# PROC099B_LP_Connector.net
KiCad netlist of a schematic drawn in Altium Designer
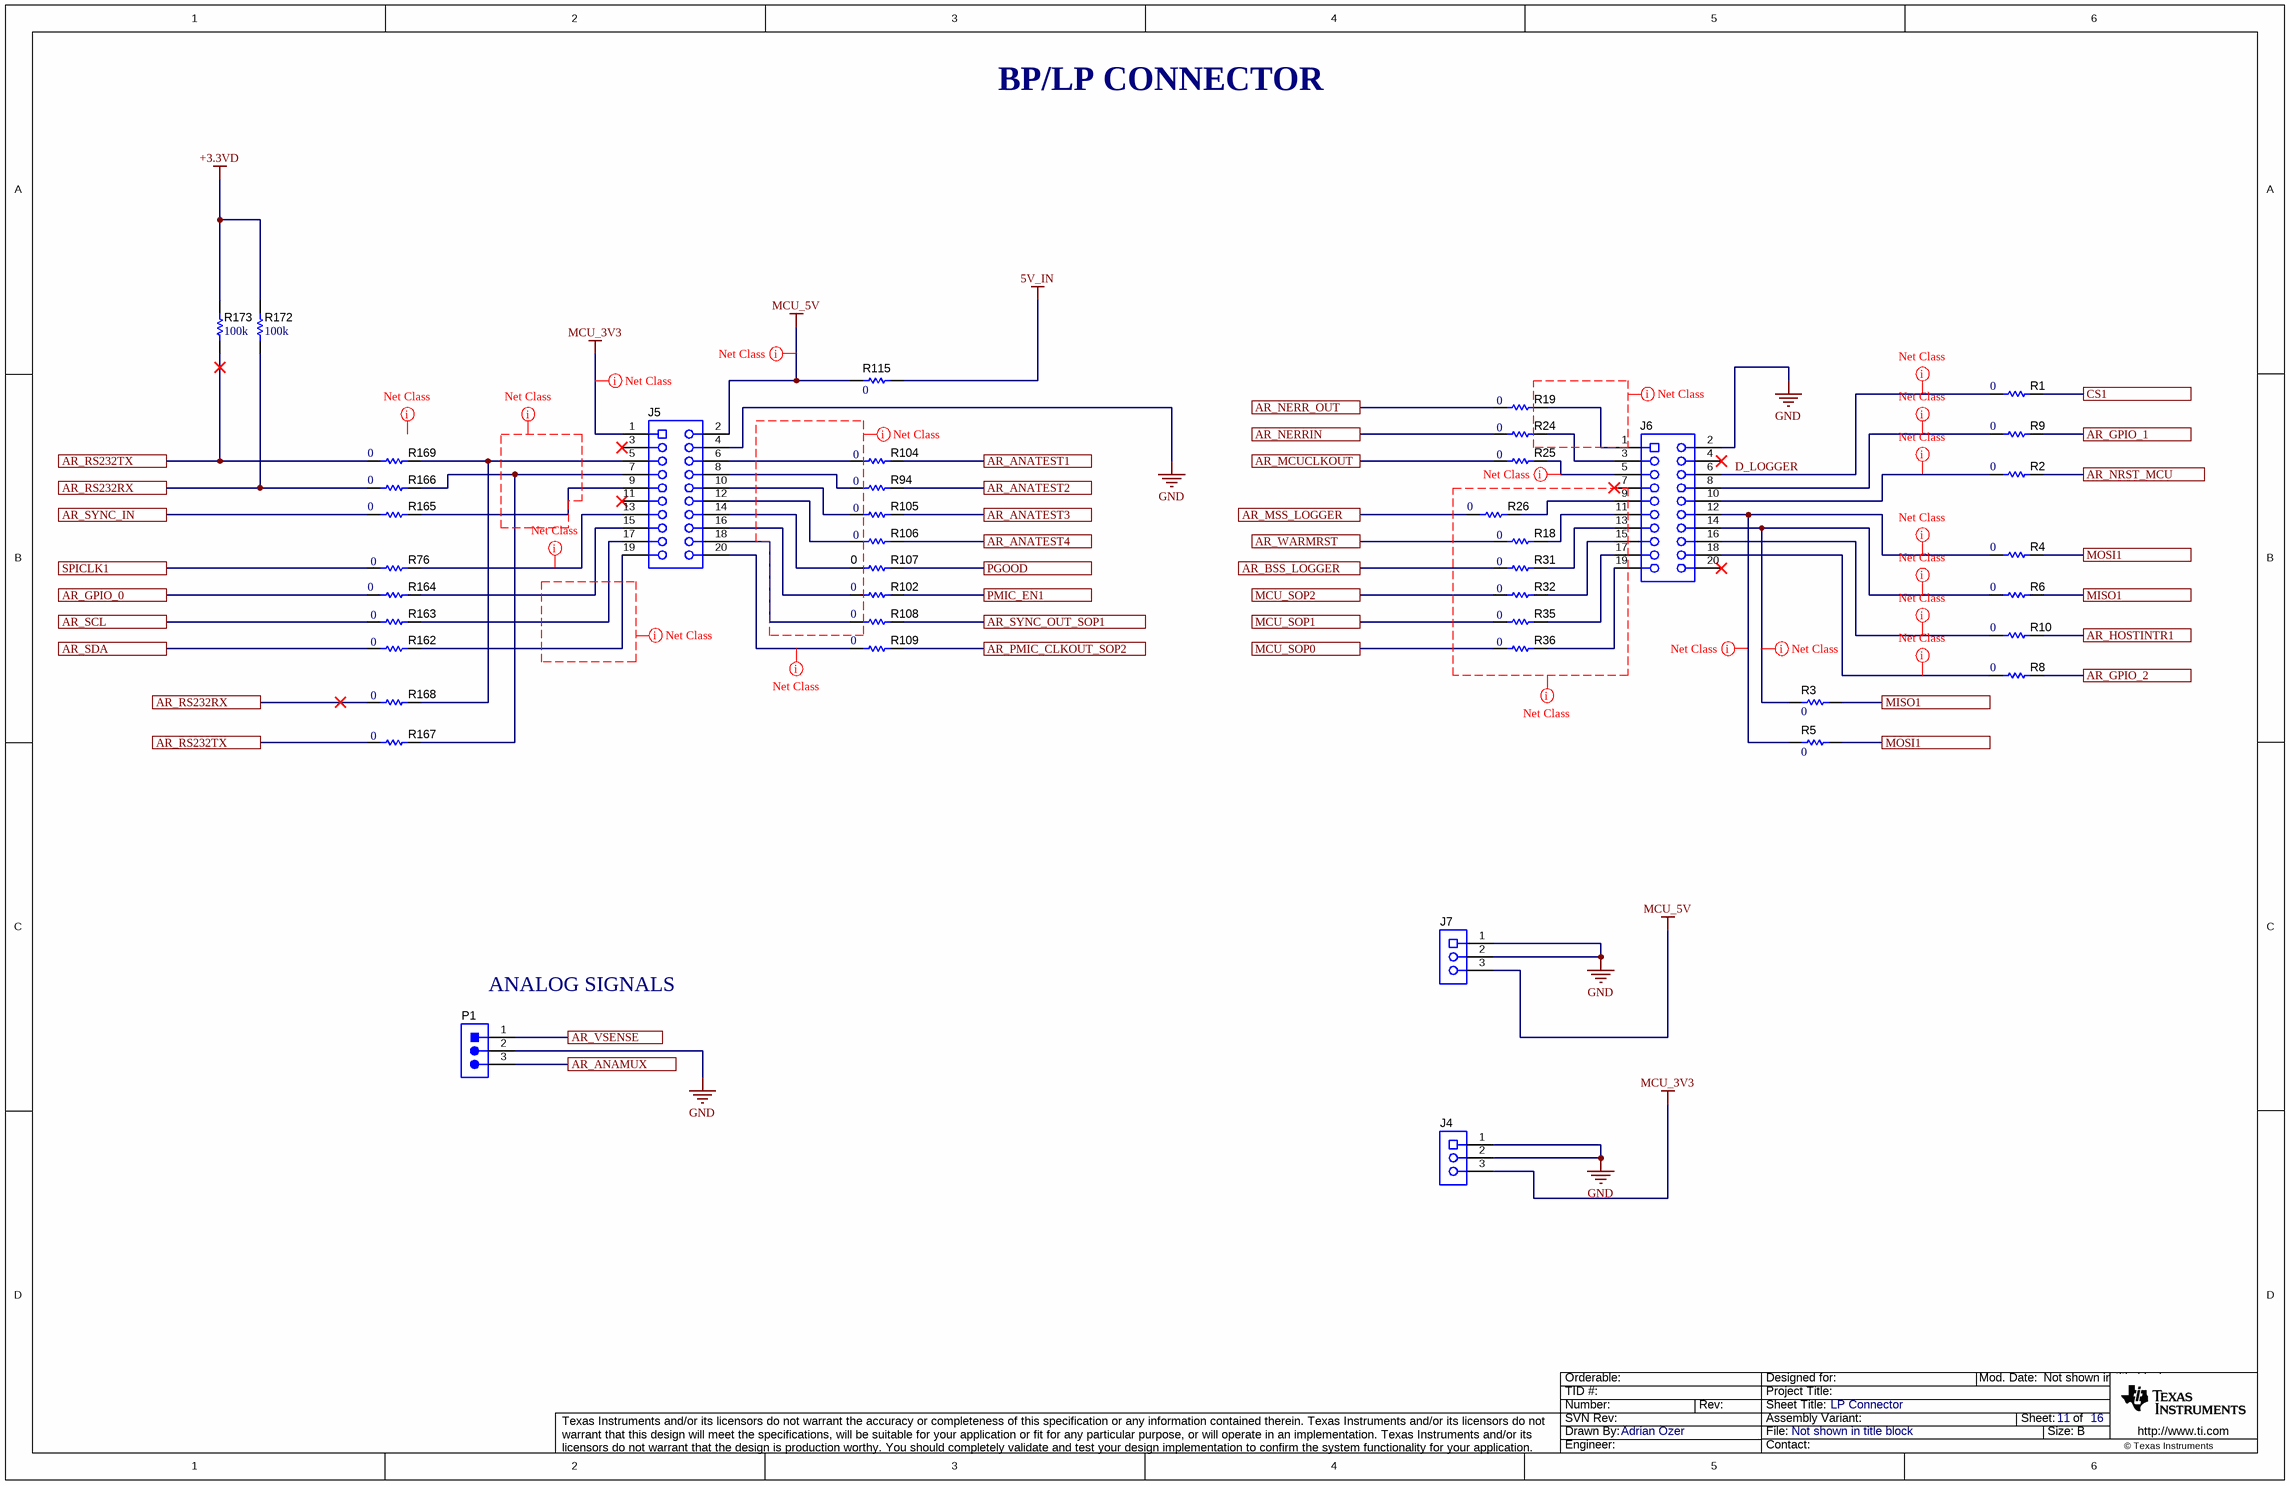
[diagram p0: PROC099B_LP Connector.SchDoc]

(export (version "E")
  (design (tool "Eeschema 10.0.6"))
  (components
    (comp (ref "J4")
      (value "SSM-103-S-SV")
      (footprint "Samtec_SSM-103-x-SV")
      (description "Receptacle, 2.54mm, 3x1, Gold with Tin tail, SMT")
      (fields (field (name "MANUFACTURER") "Samtec"))
      (libsource (lib "Altium Vault - TI") (part "CMP-0078183-1"))
    )
    (comp (ref "J5")
      (value "SSM-110-S-DV")
      (footprint "Samtec_SSM-110-x-DV")
      (description "Receptacle, 2.54mm, 10x2, Gold with Tin tail, SMT")
      (fields (field (name "MANUFACTURER") "Samtec"))
      (libsource (lib "Altium Vault - TI") (part "CMP-0078182-1"))
    )
    (comp (ref "J6")
      (value "SSM-110-S-DV")
      (footprint "Samtec_SSM-110-x-DV")
      (description "Receptacle, 2.54mm, 10x2, Gold with Tin tail, SMT")
      (fields (field (name "MANUFACTURER") "Samtec"))
      (libsource (lib "Altium Vault - TI") (part "CMP-0078182-1"))
    )
    (comp (ref "J7")
      (value "SSM-103-S-SV")
      (footprint "Samtec_SSM-103-x-SV")
      (description "Receptacle, 2.54mm, 3x1, Gold with Tin tail, SMT")
      (fields (field (name "MANUFACTURER") "Samtec"))
      (libsource (lib "Altium Vault - TI") (part "CMP-0078183-1"))
    )
    (comp (ref "P1")
      (value "TSW-103-07-T-S")
      (footprint "Samtec_TSW-103-07-T-S")
      (description "Header, 2.54 mm, 3x1, Tin, TH")
      (fields (field (name "MANUFACTURER") "Samtec"))
      (libsource (lib "Altium Vault - TI") (part "Header_3x1"))
    )
    (comp (ref "R1")
      (value "CRCW02010000Z0ED")
      (footprint "0201_Silk")
      (description "RES, 0, 5%, 0.05 W, 0201")
      (fields (field (name "MANUFACTURER") "Vishay-Dale") (field (name "VALUEDISPLAYED") "0"))
      (libsource (lib "Altium Vault - TI") (part "Resistor"))
    )
    (comp (ref "R2")
      (value "CRCW02010000Z0ED")
      (footprint "0201_Silk")
      (description "RES, 0, 5%, 0.05 W, 0201")
      (fields (field (name "MANUFACTURER") "Vishay-Dale") (field (name "VALUEDISPLAYED") "0"))
      (libsource (lib "Altium Vault - TI") (part "Resistor"))
    )
    (comp (ref "R3")
      (value "CRCW02010000Z0ED")
      (footprint "0201_Silk")
      (description "RES, 0, 5%, 0.05 W, 0201")
      (fields (field (name "MANUFACTURER") "Vishay-Dale") (field (name "VALUEDISPLAYED") "0"))
      (libsource (lib "Altium Vault - TI") (part "Resistor"))
    )
    (comp (ref "R4")
      (value "CRCW02010000Z0ED")
      (footprint "0201_Silk")
      (description "RES, 0, 5%, 0.05 W, 0201")
      (fields (field (name "MANUFACTURER") "Vishay-Dale") (field (name "VALUEDISPLAYED") "0"))
      (libsource (lib "Altium Vault - TI") (part "Resistor"))
    )
    (comp (ref "R5")
      (value "CRCW02010000Z0ED")
      (footprint "0201_Silk")
      (description "RES, 0, 5%, 0.05 W, 0201")
      (fields (field (name "MANUFACTURER") "Vishay-Dale") (field (name "VALUEDISPLAYED") "0"))
      (libsource (lib "Altium Vault - TI") (part "Resistor"))
    )
    (comp (ref "R6")
      (value "CRCW02010000Z0ED")
      (footprint "0201_Silk")
      (description "RES, 0, 5%, 0.05 W, 0201")
      (fields (field (name "MANUFACTURER") "Vishay-Dale") (field (name "VALUEDISPLAYED") "0"))
      (libsource (lib "Altium Vault - TI") (part "Resistor"))
    )
    (comp (ref "R8")
      (value "CRCW02010000Z0ED")
      (footprint "0201_Silk")
      (description "RES, 0, 5%, 0.05 W, 0201")
      (fields (field (name "MANUFACTURER") "Vishay-Dale") (field (name "VALUEDISPLAYED") "0"))
      (libsource (lib "Altium Vault - TI") (part "Resistor"))
    )
    (comp (ref "R9")
      (value "CRCW02010000Z0ED")
      (footprint "0201_Silk")
      (description "RES, 0, 5%, 0.05 W, 0201")
      (fields (field (name "MANUFACTURER") "Vishay-Dale") (field (name "VALUEDISPLAYED") "0"))
      (libsource (lib "Altium Vault - TI") (part "Resistor"))
    )
    (comp (ref "R10")
      (value "CRCW02010000Z0ED")
      (footprint "0201_Silk")
      (description "RES, 0, 5%, 0.05 W, 0201")
      (fields (field (name "MANUFACTURER") "Vishay-Dale") (field (name "VALUEDISPLAYED") "0"))
      (libsource (lib "Altium Vault - TI") (part "Resistor"))
    )
    (comp (ref "R18")
      (value "CRCW02010000Z0ED")
      (footprint "0201_Silk")
      (description "RES, 0, 5%, 0.05 W, 0201")
      (fields (field (name "MANUFACTURER") "Vishay-Dale") (field (name "VALUEDISPLAYED") "0"))
      (libsource (lib "Altium Vault - TI") (part "Resistor"))
    )
    (comp (ref "R19")
      (value "CRCW02010000Z0ED")
      (footprint "0201_Silk")
      (description "RES, 0, 5%, 0.05 W, 0201")
      (fields (field (name "MANUFACTURER") "Vishay-Dale") (field (name "VALUEDISPLAYED") "0"))
      (libsource (lib "Altium Vault - TI") (part "Resistor"))
    )
    (comp (ref "R24")
      (value "CRCW02010000Z0ED")
      (footprint "0201_Silk")
      (description "RES, 0, 5%, 0.05 W, 0201")
      (fields (field (name "MANUFACTURER") "Vishay-Dale") (field (name "VALUEDISPLAYED") "0"))
      (libsource (lib "Altium Vault - TI") (part "Resistor"))
    )
    (comp (ref "R25")
      (value "CRCW02010000Z0ED")
      (footprint "0201_Silk")
      (description "RES, 0, 5%, 0.05 W, 0201")
      (fields (field (name "MANUFACTURER") "Vishay-Dale") (field (name "VALUEDISPLAYED") "0"))
      (libsource (lib "Altium Vault - TI") (part "Resistor"))
    )
    (comp (ref "R26")
      (value "CRCW02010000Z0ED")
      (footprint "0201_Silk")
      (description "RES, 0, 5%, 0.05 W, 0201")
      (fields (field (name "MANUFACTURER") "Vishay-Dale") (field (name "VALUEDISPLAYED") "0"))
      (libsource (lib "Altium Vault - TI") (part "Resistor"))
    )
    (comp (ref "R31")
      (value "CRCW02010000Z0ED")
      (footprint "0201_Silk")
      (description "RES, 0, 5%, 0.05 W, 0201")
      (fields (field (name "MANUFACTURER") "Vishay-Dale") (field (name "VALUEDISPLAYED") "0"))
      (libsource (lib "Altium Vault - TI") (part "Resistor"))
    )
    (comp (ref "R32")
      (value "CRCW02010000Z0ED")
      (footprint "0201_Silk")
      (description "RES, 0, 5%, 0.05 W, 0201")
      (fields (field (name "MANUFACTURER") "Vishay-Dale") (field (name "VALUEDISPLAYED") "0"))
      (libsource (lib "Altium Vault - TI") (part "Resistor"))
    )
    (comp (ref "R35")
      (value "CRCW02010000Z0ED")
      (footprint "0201_Silk")
      (description "RES, 0, 5%, 0.05 W, 0201")
      (fields (field (name "MANUFACTURER") "Vishay-Dale") (field (name "VALUEDISPLAYED") "0"))
      (libsource (lib "Altium Vault - TI") (part "Resistor"))
    )
    (comp (ref "R36")
      (value "CRCW02010000Z0ED")
      (footprint "0201_Silk")
      (description "RES, 0, 5%, 0.05 W, 0201")
      (fields (field (name "MANUFACTURER") "Vishay-Dale") (field (name "VALUEDISPLAYED") "0"))
      (libsource (lib "Altium Vault - TI") (part "Resistor"))
    )
    (comp (ref "R76")
      (value "CRCW02010000Z0ED")
      (footprint "0201_Silk")
      (description "RES, 0, 5%, 0.05 W, 0201")
      (fields (field (name "MANUFACTURER") "Vishay-Dale") (field (name "VALUEDISPLAYED") "0"))
      (libsource (lib "Altium Vault - TI") (part "CMP-0027008-4"))
    )
    (comp (ref "R94")
      (value "CRCW02010000Z0ED")
      (footprint "0201_Silk")
      (description "RES, 0, 5%, 0.05 W, 0201")
      (fields (field (name "MANUFACTURER") "Vishay-Dale") (field (name "VALUEDISPLAYED") "0"))
      (libsource (lib "Altium Vault - TI") (part "Resistor"))
    )
    (comp (ref "R102")
      (value "CRCW02010000Z0ED")
      (footprint "0201_Silk")
      (description "RES, 0, 5%, 0.05 W, 0201")
      (fields (field (name "MANUFACTURER") "Vishay-Dale") (field (name "VALUEDISPLAYED") "0"))
      (libsource (lib "Altium Vault - TI") (part "Resistor"))
    )
    (comp (ref "R104")
      (value "CRCW02010000Z0ED")
      (footprint "0201_Silk")
      (description "RES, 0, 5%, 0.05 W, 0201")
      (fields (field (name "MANUFACTURER") "Vishay-Dale") (field (name "VALUEDISPLAYED") "0"))
      (libsource (lib "Altium Vault - TI") (part "CMP-0027008-4"))
    )
    (comp (ref "R105")
      (value "CRCW02010000Z0ED")
      (footprint "0201_Silk")
      (description "RES, 0, 5%, 0.05 W, 0201")
      (fields (field (name "MANUFACTURER") "Vishay-Dale") (field (name "VALUEDISPLAYED") "0"))
      (libsource (lib "Altium Vault - TI") (part "Resistor"))
    )
    (comp (ref "R106")
      (value "CRCW02010000Z0ED")
      (footprint "0201_Silk")
      (description "RES, 0, 5%, 0.05 W, 0201")
      (fields (field (name "MANUFACTURER") "Vishay-Dale") (field (name "VALUEDISPLAYED") "0"))
      (libsource (lib "Altium Vault - TI") (part "Resistor"))
    )
    (comp (ref "R107")
      (value "ERJ-2GE0R00X")
      (footprint "0402L")
      (description "RES, 0, 5%, 0.063 W, 0402")
      (fields
        (field (name "MANUFACTURER") "Panasonic")
        (field (name "VALUEDISPLAYED") "0")
        (field (name "PUBLISHER") "Texas Instruments")
      )
      (libsource (lib "Altium Vault - TI") (part "Resistor"))
    )
    (comp (ref "R108")
      (value "CRCW02010000Z0ED")
      (footprint "0201_Silk")
      (description "RES, 0, 5%, 0.05 W, 0201")
      (fields (field (name "MANUFACTURER") "Vishay-Dale") (field (name "VALUEDISPLAYED") "0"))
      (libsource (lib "Altium Vault - TI") (part "Resistor"))
    )
    (comp (ref "R109")
      (value "CRCW02010000Z0ED")
      (footprint "0201_Silk")
      (description "RES, 0, 5%, 0.05 W, 0201")
      (fields (field (name "MANUFACTURER") "Vishay-Dale") (field (name "VALUEDISPLAYED") "0"))
      (libsource (lib "Altium Vault - TI") (part "Resistor"))
    )
    (comp (ref "R115")
      (value "CRCW20100000Z0EF")
      (footprint "2010")
      (description "RES, 0, 5%, 0.75 W, AEC-Q200 Grade 0, 2010")
      (fields (field (name "MANUFACTURER") "Vishay-Dale") (field (name "VALUEDISPLAYED") "0"))
      (libsource (lib "Altium Vault - TI") (part "Resistor"))
    )
    (comp (ref "R162")
      (value "CRCW02010000Z0ED")
      (footprint "0201_Silk")
      (description "RES, 0, 5%, 0.05 W, 0201")
      (fields (field (name "MANUFACTURER") "Vishay-Dale") (field (name "VALUEDISPLAYED") "0"))
      (libsource (lib "Altium Vault - TI") (part "Resistor"))
    )
    (comp (ref "R163")
      (value "CRCW02010000Z0ED")
      (footprint "0201_Silk")
      (description "RES, 0, 5%, 0.05 W, 0201")
      (fields (field (name "MANUFACTURER") "Vishay-Dale") (field (name "VALUEDISPLAYED") "0"))
      (libsource (lib "Altium Vault - TI") (part "Resistor"))
    )
    (comp (ref "R164")
      (value "CRCW02010000Z0ED")
      (footprint "0201_Silk")
      (description "RES, 0, 5%, 0.05 W, 0201")
      (fields (field (name "MANUFACTURER") "Vishay-Dale") (field (name "VALUEDISPLAYED") "0"))
      (libsource (lib "Altium Vault - TI") (part "Resistor"))
    )
    (comp (ref "R165")
      (value "CRCW02010000Z0ED")
      (footprint "0201_Silk")
      (description "RES, 0, 5%, 0.05 W, 0201")
      (fields (field (name "MANUFACTURER") "Vishay-Dale") (field (name "VALUEDISPLAYED") "0"))
      (libsource (lib "Altium Vault - TI") (part "Resistor"))
    )
    (comp (ref "R166")
      (value "CRCW02010000Z0ED")
      (footprint "0201_Silk")
      (description "RES, 0, 5%, 0.05 W, 0201")
      (fields (field (name "MANUFACTURER") "Vishay-Dale") (field (name "VALUEDISPLAYED") "0"))
      (libsource (lib "Altium Vault - TI") (part "Resistor"))
    )
    (comp (ref "R167")
      (value "CRCW02010000Z0ED")
      (footprint "0201_Silk")
      (description "RES, 0, 5%, 0.05 W, 0201")
      (fields (field (name "MANUFACTURER") "Vishay-Dale") (field (name "VALUEDISPLAYED") "0"))
      (libsource (lib "Altium Vault - TI") (part "Resistor"))
    )
    (comp (ref "R168")
      (value "CRCW02010000Z0ED")
      (footprint "0201_Silk")
      (description "RES, 0, 5%, 0.05 W, 0201")
      (fields (field (name "MANUFACTURER") "Vishay-Dale") (field (name "VALUEDISPLAYED") "0"))
      (libsource (lib "Altium Vault - TI") (part "Resistor"))
    )
    (comp (ref "R169")
      (value "CRCW02010000Z0ED")
      (footprint "0201_Silk")
      (description "RES, 0, 5%, 0.05 W, 0201")
      (fields (field (name "MANUFACTURER") "Vishay-Dale") (field (name "VALUEDISPLAYED") "0"))
      (libsource (lib "Altium Vault - TI") (part "Resistor"))
    )
    (comp (ref "R172")
      (value "CRCW0402100KFKED")
      (footprint "0402L")
      (description "RES, 100 k, 1%, 0.063 W, AEC-Q200 Grade 0, 0402")
      (fields (field (name "MANUFACTURER") "Vishay-Dale") (field (name "VALUEDISPLAYED") "100k"))
      (libsource (lib "Altium Vault - TI") (part "Resistor"))
    )
    (comp (ref "R173")
      (value "CRCW0402100KFKED")
      (footprint "0402L")
      (description "RES, 100 k, 1%, 0.063 W, AEC-Q200 Grade 0, 0402")
      (fields (field (name "MANUFACTURER") "Vishay-Dale") (field (name "VALUEDISPLAYED") "100k"))
      (libsource (lib "Altium Vault - TI") (part "Resistor"))
    )
  )
  (nets
    (net (code "1") (name "+3.3VD") (class "Default")
      (node (ref "R172") (pin "2") (pinfunction "2_2") (pintype "passive"))
      (node (ref "R173") (pin "2") (pinfunction "2_2") (pintype "passive"))
    )
    (net (code "2") (name "/AR_ANAMUX") (class "Default")
      (node (ref "P1") (pin "3") (pinfunction "3_3") (pintype "passive"))
    )
    (net (code "3") (name "/AR_ANATEST1") (class "Default")
      (node (ref "R104") (pin "2") (pinfunction "2_2") (pintype "passive"))
    )
    (net (code "4") (name "/AR_ANATEST2") (class "Default")
      (node (ref "R94") (pin "2") (pinfunction "2_2") (pintype "passive"))
    )
    (net (code "5") (name "/AR_ANATEST3") (class "Default")
      (node (ref "R105") (pin "2") (pinfunction "2_2") (pintype "passive"))
    )
    (net (code "6") (name "/AR_ANATEST4") (class "Default")
      (node (ref "R106") (pin "2") (pinfunction "2_2") (pintype "passive"))
    )
    (net (code "7") (name "/AR_BSS_LOGGER") (class "Default")
      (node (ref "R31") (pin "1") (pinfunction "1_1") (pintype "passive"))
    )
    (net (code "8") (name "/AR_GPIO_0") (class "Default")
      (node (ref "R164") (pin "1") (pinfunction "1_1") (pintype "passive"))
    )
    (net (code "9") (name "/AR_GPIO_1") (class "Default")
      (node (ref "R9") (pin "2") (pinfunction "2_2") (pintype "passive"))
    )
    (net (code "10") (name "/AR_GPIO_2") (class "Default")
      (node (ref "R8") (pin "2") (pinfunction "2_2") (pintype "passive"))
    )
    (net (code "11") (name "/AR_HOSTINTR1") (class "Default")
      (node (ref "R10") (pin "2") (pinfunction "2_2") (pintype "passive"))
    )
    (net (code "12") (name "/AR_MCUCLKOUT") (class "Default")
      (node (ref "R25") (pin "1") (pinfunction "1_1") (pintype "passive"))
    )
    (net (code "13") (name "/AR_MSS_LOGGER") (class "Default")
      (node (ref "R26") (pin "1") (pinfunction "1_1") (pintype "passive"))
    )
    (net (code "14") (name "/AR_NERRIN") (class "Default")
      (node (ref "R24") (pin "1") (pinfunction "1_1") (pintype "passive"))
    )
    (net (code "15") (name "/AR_NERR_OUT") (class "Default")
      (node (ref "R19") (pin "1") (pinfunction "1_1") (pintype "passive"))
    )
    (net (code "16") (name "/AR_NRST_MCU") (class "Default")
      (node (ref "R2") (pin "2") (pinfunction "2_2") (pintype "passive"))
    )
    (net (code "17") (name "/AR_PMIC_CLKOUT_SOP2") (class "Default")
      (node (ref "R109") (pin "2") (pinfunction "2_2") (pintype "passive"))
    )
    (net (code "18") (name "/AR_RS232RX") (class "Default")
      (node (ref "R166") (pin "1") (pinfunction "1_1") (pintype "passive"))
      (node (ref "R168") (pin "1") (pinfunction "1_1") (pintype "passive"))
      (node (ref "R172") (pin "1") (pinfunction "1_1") (pintype "passive"))
    )
    (net (code "19") (name "/AR_RS232TX") (class "Default")
      (node (ref "R167") (pin "1") (pinfunction "1_1") (pintype "passive"))
      (node (ref "R169") (pin "1") (pinfunction "1_1") (pintype "passive"))
      (node (ref "R173") (pin "1") (pinfunction "1_1") (pintype "passive"))
    )
    (net (code "20") (name "/AR_SCL") (class "Default")
      (node (ref "R163") (pin "1") (pinfunction "1_1") (pintype "passive"))
    )
    (net (code "21") (name "/AR_SDA") (class "Default")
      (node (ref "R162") (pin "1") (pinfunction "1_1") (pintype "passive"))
    )
    (net (code "22") (name "/AR_SYNC_IN") (class "Default")
      (node (ref "R165") (pin "1") (pinfunction "1_1") (pintype "passive"))
    )
    (net (code "23") (name "/AR_SYNC_OUT_SOP1") (class "Default")
      (node (ref "R108") (pin "2") (pinfunction "2_2") (pintype "passive"))
    )
    (net (code "24") (name "/AR_VSENSE") (class "Default")
      (node (ref "P1") (pin "1") (pinfunction "1_1") (pintype "passive"))
    )
    (net (code "25") (name "/AR_WARMRST") (class "Default")
      (node (ref "R18") (pin "1") (pinfunction "1_1") (pintype "passive"))
    )
    (net (code "26") (name "/CS1") (class "Default")
      (node (ref "R1") (pin "2") (pinfunction "2_2") (pintype "passive"))
    )
    (net (code "27") (name "/D_LOGGER") (class "Default")
      (node (ref "J6") (pin "6") (pinfunction "6_6") (pintype "passive"))
      (node (ref "R1") (pin "1") (pinfunction "1_1") (pintype "passive"))
    )
    (net (code "28") (name "/MCU_SOP0") (class "Default")
      (node (ref "R36") (pin "1") (pinfunction "1_1") (pintype "passive"))
    )
    (net (code "29") (name "/MCU_SOP1") (class "Default")
      (node (ref "R35") (pin "1") (pinfunction "1_1") (pintype "passive"))
    )
    (net (code "30") (name "/MCU_SOP2") (class "Default")
      (node (ref "R32") (pin "1") (pinfunction "1_1") (pintype "passive"))
    )
    (net (code "31") (name "/MISO1") (class "Default")
      (node (ref "R3") (pin "2") (pinfunction "2_2") (pintype "passive"))
      (node (ref "R6") (pin "2") (pinfunction "2_2") (pintype "passive"))
    )
    (net (code "32") (name "/MOSI1") (class "Default")
      (node (ref "R4") (pin "2") (pinfunction "2_2") (pintype "passive"))
      (node (ref "R5") (pin "2") (pinfunction "2_2") (pintype "passive"))
    )
    (net (code "33") (name "/PGOOD") (class "Default")
      (node (ref "R107") (pin "2") (pinfunction "2_2") (pintype "passive"))
    )
    (net (code "34") (name "/PMIC_EN1") (class "Default")
      (node (ref "R102") (pin "2") (pinfunction "2_2") (pintype "passive"))
    )
    (net (code "35") (name "/SPICLK1") (class "Default")
      (node (ref "R76") (pin "1") (pinfunction "1_1") (pintype "passive"))
    )
    (net (code "36") (name "5V_IN") (class "Default")
      (node (ref "R115") (pin "2") (pinfunction "2_2") (pintype "passive"))
    )
    (net (code "37") (name "GND") (class "Default")
      (node (ref "J4") (pin "1") (pinfunction "1_1") (pintype "passive"))
      (node (ref "J4") (pin "2") (pinfunction "2_2") (pintype "passive"))
      (node (ref "J5") (pin "4") (pinfunction "4_4") (pintype "passive"))
      (node (ref "J6") (pin "2") (pinfunction "2_2") (pintype "passive"))
      (node (ref "J7") (pin "1") (pinfunction "1_1") (pintype "passive"))
      (node (ref "J7") (pin "2") (pinfunction "2_2") (pintype "passive"))
      (node (ref "P1") (pin "2") (pinfunction "2_2") (pintype "passive"))
    )
    (net (code "38") (name "MCU_3V3") (class "Default")
      (node (ref "J4") (pin "3") (pinfunction "3_3") (pintype "passive"))
      (node (ref "J5") (pin "1") (pinfunction "1_1") (pintype "passive"))
    )
    (net (code "39") (name "MCU_5V") (class "Default")
      (node (ref "J5") (pin "2") (pinfunction "2_2") (pintype "passive"))
      (node (ref "J7") (pin "3") (pinfunction "3_3") (pintype "passive"))
      (node (ref "R115") (pin "1") (pinfunction "1_1") (pintype "passive"))
    )
    (net (code "40") (name "Net-(J5-Pad5)") (class "Default")
      (node (ref "J5") (pin "5") (pinfunction "5_5") (pintype "passive"))
      (node (ref "R168") (pin "2") (pinfunction "2_2") (pintype "passive"))
      (node (ref "R169") (pin "2") (pinfunction "2_2") (pintype "passive"))
    )
    (net (code "41") (name "Net-(J5-Pad6)") (class "Default")
      (node (ref "J5") (pin "6") (pinfunction "6_6") (pintype "passive"))
      (node (ref "R104") (pin "1") (pinfunction "1_1") (pintype "passive"))
    )
    (net (code "42") (name "Net-(J5-Pad7)") (class "Default")
      (node (ref "J5") (pin "7") (pinfunction "7_7") (pintype "passive"))
      (node (ref "R166") (pin "2") (pinfunction "2_2") (pintype "passive"))
      (node (ref "R167") (pin "2") (pinfunction "2_2") (pintype "passive"))
    )
    (net (code "43") (name "Net-(J5-Pad8)") (class "Default")
      (node (ref "J5") (pin "8") (pinfunction "8_8") (pintype "passive"))
      (node (ref "R94") (pin "1") (pinfunction "1_1") (pintype "passive"))
    )
    (net (code "44") (name "Net-(J5-Pad9)") (class "Default")
      (node (ref "J5") (pin "9") (pinfunction "9_9") (pintype "passive"))
      (node (ref "R165") (pin "2") (pinfunction "2_2") (pintype "passive"))
    )
    (net (code "45") (name "Net-(J5-Pad10)") (class "Default")
      (node (ref "J5") (pin "10") (pinfunction "10_10") (pintype "passive"))
      (node (ref "R105") (pin "1") (pinfunction "1_1") (pintype "passive"))
    )
    (net (code "46") (name "Net-(J5-Pad12)") (class "Default")
      (node (ref "J5") (pin "12") (pinfunction "12_12") (pintype "passive"))
      (node (ref "R106") (pin "1") (pinfunction "1_1") (pintype "passive"))
    )
    (net (code "47") (name "Net-(J5-Pad13)") (class "Default")
      (node (ref "J5") (pin "13") (pinfunction "13_13") (pintype "passive"))
      (node (ref "R76") (pin "2") (pinfunction "2_2") (pintype "passive"))
    )
    (net (code "48") (name "Net-(J5-Pad14)") (class "Default")
      (node (ref "J5") (pin "14") (pinfunction "14_14") (pintype "passive"))
      (node (ref "R107") (pin "1") (pinfunction "1_1") (pintype "passive"))
    )
    (net (code "49") (name "Net-(J5-Pad15)") (class "Default")
      (node (ref "J5") (pin "15") (pinfunction "15_15") (pintype "passive"))
      (node (ref "R164") (pin "2") (pinfunction "2_2") (pintype "passive"))
    )
    (net (code "50") (name "Net-(J5-Pad16)") (class "Default")
      (node (ref "J5") (pin "16") (pinfunction "16_16") (pintype "passive"))
      (node (ref "R102") (pin "1") (pinfunction "1_1") (pintype "passive"))
    )
    (net (code "51") (name "Net-(J5-Pad17)") (class "Default")
      (node (ref "J5") (pin "17") (pinfunction "17_17") (pintype "passive"))
      (node (ref "R163") (pin "2") (pinfunction "2_2") (pintype "passive"))
    )
    (net (code "52") (name "Net-(J5-Pad18)") (class "Default")
      (node (ref "J5") (pin "18") (pinfunction "18_18") (pintype "passive"))
      (node (ref "R108") (pin "1") (pinfunction "1_1") (pintype "passive"))
    )
    (net (code "53") (name "Net-(J5-Pad19)") (class "Default")
      (node (ref "J5") (pin "19") (pinfunction "19_19") (pintype "passive"))
      (node (ref "R162") (pin "2") (pinfunction "2_2") (pintype "passive"))
    )
    (net (code "54") (name "Net-(J5-Pad20)") (class "Default")
      (node (ref "J5") (pin "20") (pinfunction "20_20") (pintype "passive"))
      (node (ref "R109") (pin "1") (pinfunction "1_1") (pintype "passive"))
    )
    (net (code "55") (name "Net-(J6-Pad1)") (class "Default")
      (node (ref "J6") (pin "1") (pinfunction "1_1") (pintype "passive"))
      (node (ref "R19") (pin "2") (pinfunction "2_2") (pintype "passive"))
    )
    (net (code "56") (name "Net-(J6-Pad3)") (class "Default")
      (node (ref "J6") (pin "3") (pinfunction "3_3") (pintype "passive"))
      (node (ref "R24") (pin "2") (pinfunction "2_2") (pintype "passive"))
    )
    (net (code "57") (name "Net-(J6-Pad5)") (class "Default")
      (node (ref "J6") (pin "5") (pinfunction "5_5") (pintype "passive"))
      (node (ref "R25") (pin "2") (pinfunction "2_2") (pintype "passive"))
    )
    (net (code "58") (name "Net-(J6-Pad8)") (class "Default")
      (node (ref "J6") (pin "8") (pinfunction "8_8") (pintype "passive"))
      (node (ref "R9") (pin "1") (pinfunction "1_1") (pintype "passive"))
    )
    (net (code "59") (name "Net-(J6-Pad9)") (class "Default")
      (node (ref "J6") (pin "9") (pinfunction "9_9") (pintype "passive"))
      (node (ref "R26") (pin "2") (pinfunction "2_2") (pintype "passive"))
    )
    (net (code "60") (name "Net-(J6-Pad10)") (class "Default")
      (node (ref "J6") (pin "10") (pinfunction "10_10") (pintype "passive"))
      (node (ref "R2") (pin "1") (pinfunction "1_1") (pintype "passive"))
    )
    (net (code "61") (name "Net-(J6-Pad11)") (class "Default")
      (node (ref "J6") (pin "11") (pinfunction "11_11") (pintype "passive"))
      (node (ref "R18") (pin "2") (pinfunction "2_2") (pintype "passive"))
    )
    (net (code "62") (name "Net-(J6-Pad12)") (class "Default")
      (node (ref "J6") (pin "12") (pinfunction "12_12") (pintype "passive"))
      (node (ref "R4") (pin "1") (pinfunction "1_1") (pintype "passive"))
      (node (ref "R5") (pin "1") (pinfunction "1_1") (pintype "passive"))
    )
    (net (code "63") (name "Net-(J6-Pad13)") (class "Default")
      (node (ref "J6") (pin "13") (pinfunction "13_13") (pintype "passive"))
      (node (ref "R31") (pin "2") (pinfunction "2_2") (pintype "passive"))
    )
    (net (code "64") (name "Net-(J6-Pad14)") (class "Default")
      (node (ref "J6") (pin "14") (pinfunction "14_14") (pintype "passive"))
      (node (ref "R3") (pin "1") (pinfunction "1_1") (pintype "passive"))
      (node (ref "R6") (pin "1") (pinfunction "1_1") (pintype "passive"))
    )
    (net (code "65") (name "Net-(J6-Pad15)") (class "Default")
      (node (ref "J6") (pin "15") (pinfunction "15_15") (pintype "passive"))
      (node (ref "R32") (pin "2") (pinfunction "2_2") (pintype "passive"))
    )
    (net (code "66") (name "Net-(J6-Pad16)") (class "Default")
      (node (ref "J6") (pin "16") (pinfunction "16_16") (pintype "passive"))
      (node (ref "R10") (pin "1") (pinfunction "1_1") (pintype "passive"))
    )
    (net (code "67") (name "Net-(J6-Pad17)") (class "Default")
      (node (ref "J6") (pin "17") (pinfunction "17_17") (pintype "passive"))
      (node (ref "R35") (pin "2") (pinfunction "2_2") (pintype "passive"))
    )
    (net (code "68") (name "Net-(J6-Pad18)") (class "Default")
      (node (ref "J6") (pin "18") (pinfunction "18_18") (pintype "passive"))
      (node (ref "R8") (pin "1") (pinfunction "1_1") (pintype "passive"))
    )
    (net (code "69") (name "Net-(J6-Pad19)") (class "Default")
      (node (ref "J6") (pin "19") (pinfunction "19_19") (pintype "passive"))
      (node (ref "R36") (pin "2") (pinfunction "2_2") (pintype "passive"))
    )
    (net (code "70") (name "unconnected-(J5-Pad3)") (class "Default")
      (node (ref "J5") (pin "3") (pinfunction "3_3") (pintype "passive+no_connect"))
    )
    (net (code "71") (name "unconnected-(J5-Pad11)") (class "Default")
      (node (ref "J5") (pin "11") (pinfunction "11_11") (pintype "passive+no_connect"))
    )
    (net (code "72") (name "unconnected-(J6-Pad4)") (class "Default")
      (node (ref "J6") (pin "4") (pinfunction "4_4") (pintype "passive+no_connect"))
    )
    (net (code "73") (name "unconnected-(J6-Pad7)") (class "Default")
      (node (ref "J6") (pin "7") (pinfunction "7_7") (pintype "passive+no_connect"))
    )
    (net (code "74") (name "unconnected-(J6-Pad20)") (class "Default")
      (node (ref "J6") (pin "20") (pinfunction "20_20") (pintype "passive+no_connect"))
    )
  )
)
